# POWER_2_1.net
KiCad netlist of a schematic drawn in Altium Designer
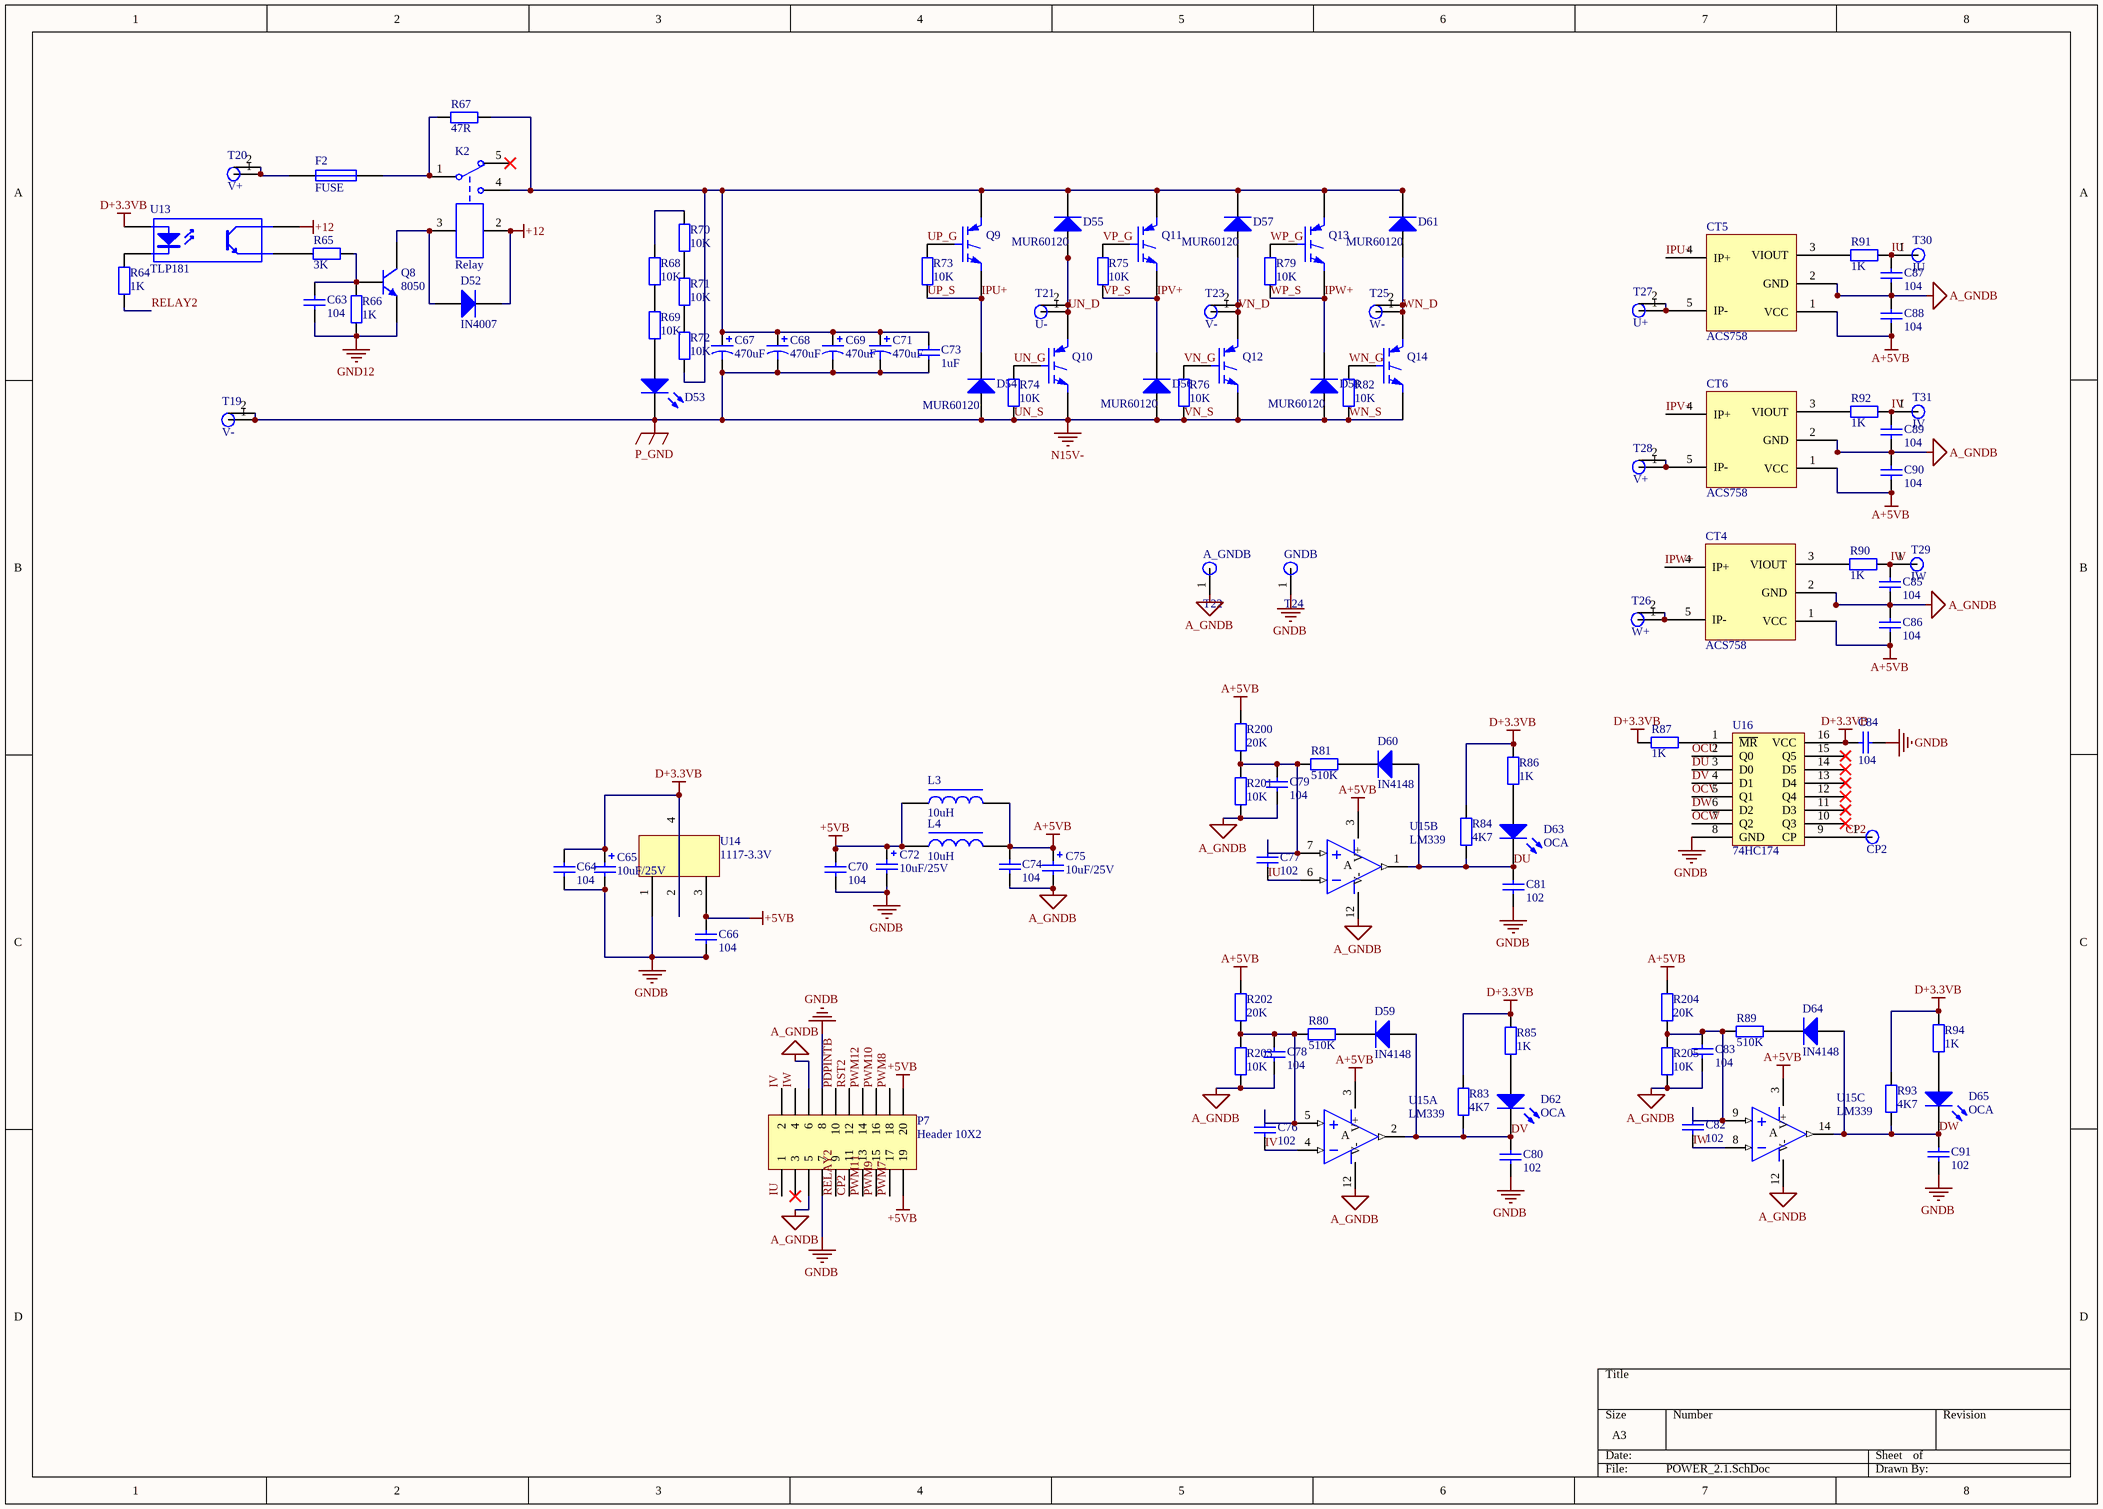
[diagram p0: POWER_2.1.SchDoc]

(export (version "E")
  (design (tool "Eeschema 10.0.6"))
  (components
    (comp (ref "C63")
      (value "104")
      (footprint "C2012-0805")
      (description "普通电容")
      (libsource (lib "Mylib") (part "Cap"))
    )
    (comp (ref "C64")
      (value "104")
      (footprint "C2012-0805")
      (description "普通电容")
      (libsource (lib "*") (part "Cap"))
    )
    (comp (ref "C65")
      (value "10uF/25V")
      (footprint "C_10UF/25V")
      (description "钽电解")
      (libsource (lib "Mylib") (part "Cap tan"))
    )
    (comp (ref "C66")
      (value "104")
      (footprint "C2012-0805")
      (description "普通电容")
      (libsource (lib "*") (part "Cap"))
    )
    (comp (ref "C67")
      (value "470uF")
      (footprint "Rb400mil-450V")
      (description "大电解电容")
      (libsource (lib "Mylib") (part "Cap pol1"))
    )
    (comp (ref "C68")
      (value "470uF")
      (footprint "Rb400mil-450V")
      (description "大电解电容")
      (libsource (lib "Mylib") (part "Cap pol1"))
    )
    (comp (ref "C69")
      (value "470uF")
      (footprint "Rb400mil-450V")
      (description "大电解电容")
      (libsource (lib "Mylib") (part "Cap pol1"))
    )
    (comp (ref "C70")
      (value "104")
      (footprint "C2012-0805")
      (description "普通电容")
      (libsource (lib "*") (part "Cap"))
    )
    (comp (ref "C71")
      (value "470uF")
      (footprint "Rb400mil-450V")
      (description "大电解电容")
      (libsource (lib "Mylib") (part "Cap pol1"))
    )
    (comp (ref "C72")
      (value "10uF/25V")
      (footprint "C_10UF/25V")
      (description "钽电解")
      (libsource (lib "Mylib") (part "Cap tan"))
    )
    (comp (ref "C73")
      (value "1uF")
      (footprint "Rb800mil")
      (description "CBB电容")
      (libsource (lib "Mylib") (part "Cap CBB"))
    )
    (comp (ref "C74")
      (value "104")
      (footprint "C2012-0805")
      (description "普通电容")
      (libsource (lib "*") (part "Cap"))
    )
    (comp (ref "C75")
      (value "10uF/25V")
      (footprint "C_10UF/25V")
      (description "钽电解")
      (libsource (lib "Mylib") (part "Cap tan"))
    )
    (comp (ref "C76")
      (value "102")
      (footprint "C2012-0805")
      (description "普通电容")
      (libsource (lib "*") (part "Cap"))
    )
    (comp (ref "C77")
      (value "102")
      (footprint "C2012-0805")
      (description "普通电容")
      (libsource (lib "*") (part "Cap"))
    )
    (comp (ref "C78")
      (value "104")
      (footprint "C2012-0805")
      (description "普通电容")
      (libsource (lib "*") (part "Cap"))
    )
    (comp (ref "C79")
      (value "104")
      (footprint "C2012-0805")
      (description "普通电容")
      (libsource (lib "*") (part "Cap"))
    )
    (comp (ref "C80")
      (value "102")
      (footprint "C2012-0805")
      (description "普通电容")
      (libsource (lib "*") (part "Cap"))
    )
    (comp (ref "C81")
      (value "102")
      (footprint "C2012-0805")
      (description "普通电容")
      (libsource (lib "*") (part "Cap"))
    )
    (comp (ref "C82")
      (value "102")
      (footprint "C2012-0805")
      (description "普通电容")
      (libsource (lib "*") (part "Cap"))
    )
    (comp (ref "C83")
      (value "104")
      (footprint "C2012-0805")
      (description "普通电容")
      (libsource (lib "*") (part "Cap"))
    )
    (comp (ref "C84")
      (value "104")
      (footprint "C2012-0805")
      (description "普通电容")
      (libsource (lib "*") (part "Cap"))
    )
    (comp (ref "C85")
      (value "104")
      (footprint "C2012-0805")
      (description "普通电容")
      (libsource (lib "Mylib") (part "Cap"))
    )
    (comp (ref "C86")
      (value "104")
      (footprint "C2012-0805")
      (description "普通电容")
      (libsource (lib "Mylib") (part "Cap"))
    )
    (comp (ref "C87")
      (value "104")
      (footprint "C2012-0805")
      (description "普通电容")
      (libsource (lib "Mylib") (part "Cap"))
    )
    (comp (ref "C88")
      (value "104")
      (footprint "C2012-0805")
      (description "普通电容")
      (libsource (lib "Mylib") (part "Cap"))
    )
    (comp (ref "C89")
      (value "104")
      (footprint "C2012-0805")
      (description "普通电容")
      (libsource (lib "Mylib") (part "Cap"))
    )
    (comp (ref "C90")
      (value "104")
      (footprint "C2012-0805")
      (description "普通电容")
      (libsource (lib "Mylib") (part "Cap"))
    )
    (comp (ref "C91")
      (value "102")
      (footprint "C2012-0805")
      (description "普通电容")
      (libsource (lib "*") (part "Cap"))
    )
    (comp (ref "CT4")
      (value "ACS758")
      (footprint "ACS758-LCB-050U-PFF")
      (libsource (lib "Mylib") (part "ACS758"))
    )
    (comp (ref "CT5")
      (value "ACS758")
      (footprint "ACS758-LCB-050U-PFF")
      (libsource (lib "Mylib") (part "ACS758"))
    )
    (comp (ref "CT6")
      (value "ACS758")
      (footprint "ACS758-LCB-050U-PFF")
      (libsource (lib "Mylib") (part "ACS758"))
    )
    (comp (ref "D52")
      (value "IN4007")
      (footprint "DIODE4007")
      (description "普通整流二极管")
      (libsource (lib "Mylib") (part "Diode IN4007"))
    )
    (comp (ref "D53") (value "LED") (footprint "LED-SMD") (libsource (lib "Mylib") (part "LED")))
    (comp (ref "D54")
      (value "MUR60120")
      (footprint "DIO40A1200V")
      (libsource (lib "Mylib") (part "Diode HFA08TB60"))
    )
    (comp (ref "D55")
      (value "MUR60120")
      (footprint "DIO40A1200V")
      (libsource (lib "Mylib") (part "Diode HFA08TB60"))
    )
    (comp (ref "D56")
      (value "MUR60120")
      (footprint "DIO40A1200V")
      (libsource (lib "Mylib") (part "Diode HFA08TB60"))
    )
    (comp (ref "D57")
      (value "MUR60120")
      (footprint "DIO40A1200V")
      (libsource (lib "Mylib") (part "Diode HFA08TB60"))
    )
    (comp (ref "D58")
      (value "MUR60120")
      (footprint "DIO40A1200V")
      (libsource (lib "Mylib") (part "Diode HFA08TB60"))
    )
    (comp (ref "D59")
      (value "IN4148")
      (footprint "IN4148")
      (description "开关二极管")
      (libsource (lib "*") (part "Diode IN4148"))
    )
    (comp (ref "D60")
      (value "IN4148")
      (footprint "IN4148")
      (description "开关二极管")
      (libsource (lib "*") (part "Diode IN4148"))
    )
    (comp (ref "D61")
      (value "MUR60120")
      (footprint "DIO40A1200V")
      (libsource (lib "Mylib") (part "Diode HFA08TB60"))
    )
    (comp (ref "D62") (value "OCA") (footprint "LED-SMD") (libsource (lib "Mylib") (part "LED")))
    (comp (ref "D63") (value "OCA") (footprint "LED-SMD") (libsource (lib "Mylib") (part "LED")))
    (comp (ref "D64")
      (value "IN4148")
      (footprint "IN4148")
      (description "开关二极管")
      (libsource (lib "*") (part "Diode IN4148"))
    )
    (comp (ref "D65") (value "OCA") (footprint "LED-SMD") (libsource (lib "Mylib") (part "LED")))
    (comp (ref "F2") (value "FUSE") (footprint "FUSE") (libsource (lib "Mylib") (part "FUSE")))
    (comp (ref "K2") (value "Relay") (footprint "Relay(30A)") (libsource (lib "Mylib") (part "Relay(30A)")))
    (comp (ref "L3") (value "10uH") (footprint "R2012-0805") (libsource (lib "*") (part "Inductor")))
    (comp (ref "L4") (value "10uH") (footprint "R2012-0805") (libsource (lib "*") (part "Inductor")))
    (comp (ref "P7")
      (value "Header 10X2")
      (footprint "HDR2X10")
      (description "Header, 10-Pin, Dual row")
      (fields (field (name "PUBLISHER") "Altium Limited"))
      (libsource (lib "Miscellaneous Connectors") (part "Header 10X2"))
    )
    (comp (ref "Q8") (value "8050") (footprint "NPN8050") (libsource (lib "Mylib") (part "NPN8050")))
    (comp (ref "Q9") (value "~") (footprint "IGBT TO247 40A 1200V") (libsource (lib "Mylib") (part "IGBT-N")))
    (comp (ref "Q10")
      (value "~")
      (footprint "IGBT TO247 40A 1200V")
      (libsource (lib "Mylib") (part "IGBT-N"))
    )
    (comp (ref "Q11")
      (value "~")
      (footprint "IGBT TO247 40A 1200V")
      (libsource (lib "Mylib") (part "IGBT-N"))
    )
    (comp (ref "Q12")
      (value "~")
      (footprint "IGBT TO247 40A 1200V")
      (libsource (lib "Mylib") (part "IGBT-N"))
    )
    (comp (ref "Q13")
      (value "~")
      (footprint "IGBT TO247 40A 1200V")
      (libsource (lib "Mylib") (part "IGBT-N"))
    )
    (comp (ref "Q14")
      (value "~")
      (footprint "IGBT TO247 40A 1200V")
      (libsource (lib "Mylib") (part "IGBT-N"))
    )
    (comp (ref "R64") (value "1K") (footprint "R2012-0805") (libsource (lib "") (part "Res_3")))
    (comp (ref "R65") (value "3K") (footprint "R2012-0805") (libsource (lib "") (part "Res_2")))
    (comp (ref "R66") (value "1K") (footprint "R2012-0805") (libsource (lib "Mylib") (part "Res")))
    (comp (ref "R67") (value "47R") (footprint "AXIAL-1*1.3") (libsource (lib "") (part "Res_2")))
    (comp (ref "R68") (value "10K") (footprint "R2012-0805") (libsource (lib "Mylib") (part "Res")))
    (comp (ref "R69") (value "10K") (footprint "R2012-0805") (libsource (lib "Mylib") (part "Res")))
    (comp (ref "R70") (value "10K") (footprint "R2012-0805") (libsource (lib "Mylib") (part "Res")))
    (comp (ref "R71") (value "10K") (footprint "R2012-0805") (libsource (lib "Mylib") (part "Res")))
    (comp (ref "R72") (value "10K") (footprint "R2012-0805") (libsource (lib "Mylib") (part "Res")))
    (comp (ref "R73") (value "10K") (footprint "R2012-0805") (libsource (lib "Mylib") (part "Res")))
    (comp (ref "R74") (value "10K") (footprint "R2012-0805") (libsource (lib "Mylib") (part "Res")))
    (comp (ref "R75") (value "10K") (footprint "R2012-0805") (libsource (lib "Mylib") (part "Res")))
    (comp (ref "R76") (value "10K") (footprint "R2012-0805") (libsource (lib "Mylib") (part "Res")))
    (comp (ref "R79") (value "10K") (footprint "R2012-0805") (libsource (lib "Mylib") (part "Res")))
    (comp (ref "R80") (value "510K") (footprint "R2012-0805") (libsource (lib "") (part "Res_1")))
    (comp (ref "R81") (value "510K") (footprint "R2012-0805") (libsource (lib "") (part "Res_1")))
    (comp (ref "R82") (value "10K") (footprint "R2012-0805") (libsource (lib "Mylib") (part "Res")))
    (comp (ref "R83") (value "4K7") (footprint "R2012-0805") (libsource (lib "") (part "Res_2")))
    (comp (ref "R84") (value "4K7") (footprint "R2012-0805") (libsource (lib "") (part "Res_2")))
    (comp (ref "R85") (value "1K") (footprint "R2012-0805") (libsource (lib "") (part "Res_2")))
    (comp (ref "R86") (value "1K") (footprint "R2012-0805") (libsource (lib "") (part "Res_2")))
    (comp (ref "R87") (value "1K") (footprint "R2012-0805") (libsource (lib "") (part "Res_1")))
    (comp (ref "R89") (value "510K") (footprint "R2012-0805") (libsource (lib "") (part "Res_1")))
    (comp (ref "R90") (value "1K") (footprint "R2012-0805") (libsource (lib "") (part "Res_1")))
    (comp (ref "R91") (value "1K") (footprint "R2012-0805") (libsource (lib "") (part "Res_1")))
    (comp (ref "R92") (value "1K") (footprint "R2012-0805") (libsource (lib "") (part "Res_1")))
    (comp (ref "R93") (value "4K7") (footprint "R2012-0805") (libsource (lib "") (part "Res_2")))
    (comp (ref "R94") (value "1K") (footprint "R2012-0805") (libsource (lib "") (part "Res_2")))
    (comp (ref "R200") (value "20K") (footprint "R2012-0805") (libsource (lib "*") (part "Res")))
    (comp (ref "R201") (value "10K") (footprint "R2012-0805") (libsource (lib "*") (part "Res")))
    (comp (ref "R202") (value "20K") (footprint "R2012-0805") (libsource (lib "*") (part "Res")))
    (comp (ref "R203") (value "10K") (footprint "R2012-0805") (libsource (lib "*") (part "Res")))
    (comp (ref "R204") (value "20K") (footprint "R2012-0805") (libsource (lib "*") (part "Res")))
    (comp (ref "R205") (value "10K") (footprint "R2012-0805") (libsource (lib "*") (part "Res")))
    (comp (ref "T19")
      (value "V-")
      (footprint "TEM")
      (description "电源端子")
      (libsource (lib "Mylib") (part "TEM"))
    )
    (comp (ref "T20")
      (value "V+")
      (footprint "TEM")
      (description "电源端子")
      (libsource (lib "Mylib") (part "TEM"))
    )
    (comp (ref "T21")
      (value "U-")
      (footprint "TEM")
      (description "电源端子")
      (libsource (lib "Mylib") (part "TEM"))
    )
    (comp (ref "T22")
      (value "A_GNDB")
      (footprint "PIN1")
      (description "测试脚")
      (libsource (lib "Mylib") (part "TP"))
    )
    (comp (ref "T23")
      (value "V-")
      (footprint "TEM")
      (description "电源端子")
      (libsource (lib "Mylib") (part "TEM"))
    )
    (comp (ref "T24")
      (value "GNDB")
      (footprint "PIN1")
      (description "测试脚")
      (libsource (lib "Mylib") (part "TP"))
    )
    (comp (ref "T25")
      (value "W-")
      (footprint "TEM")
      (description "电源端子")
      (libsource (lib "Mylib") (part "TEM"))
    )
    (comp (ref "T26")
      (value "W+")
      (footprint "TEM")
      (description "电源端子")
      (libsource (lib "Mylib") (part "TEM"))
    )
    (comp (ref "T27")
      (value "U+")
      (footprint "TEM")
      (description "电源端子")
      (libsource (lib "Mylib") (part "TEM"))
    )
    (comp (ref "T28")
      (value "V+")
      (footprint "TEM")
      (description "电源端子")
      (libsource (lib "Mylib") (part "TEM"))
    )
    (comp (ref "T29") (value "IW") (footprint "PIN1") (description "测试脚") (libsource (lib "*") (part "TP")))
    (comp (ref "T30") (value "IU") (footprint "PIN1") (description "测试脚") (libsource (lib "*") (part "TP")))
    (comp (ref "T31") (value "IV") (footprint "PIN1") (description "测试脚") (libsource (lib "*") (part "TP")))
    (comp (ref "TP5")
      (value "CP2")
      (footprint "PIN1")
      (description "测试脚")
      (libsource (lib "Mylib") (part "TP"))
    )
    (comp (ref "U13") (value "TLP181") (footprint "TLP181") (libsource (lib "Mylib") (part "TLP181")))
    (comp (ref "U14") (value "1117-3.3V") (footprint "1117-3.3V") (libsource (lib "Mylib") (part "1117")))
    (comp (ref "U15") (value "LM339") (footprint "LM339") (libsource (lib "Mylib") (part "LM339")))
    (comp (ref "U16")
      (value "74HC174")
      (footprint "74HC174")
      (description "带公共时钟和复位六D触发器")
      (libsource (lib "Mylib") (part "74HC174"))
    )
  )
  (nets
    (net (code "1") (name "+5VB") (class "Default")
      (node (ref "C66") (pin "2") (pinfunction "2_2") (pintype "passive"))
      (node (ref "C70") (pin "2") (pinfunction "2_2") (pintype "passive"))
      (node (ref "C72") (pin "1") (pinfunction "1_1") (pintype "passive"))
      (node (ref "L3") (pin "1") (pinfunction "1_1") (pintype "passive"))
      (node (ref "L4") (pin "1") (pinfunction "1_1") (pintype "passive"))
      (node (ref "P7") (pin "19") (pinfunction "19_19") (pintype "passive"))
      (node (ref "P7") (pin "20") (pinfunction "20_20") (pintype "passive"))
      (node (ref "U14") (pin "3") (pintype "passive"))
    )
    (net (code "2") (name "+12") (class "Default")
      (node (ref "D52") (pin "2") (pinfunction "K_2") (pintype "passive"))
      (node (ref "K2") (pin "2") (pinfunction "2_2") (pintype "passive"))
      (node (ref "U13") (pin "6") (pinfunction "C_6") (pintype "passive"))
    )
    (net (code "3") (name "/CP2") (class "Default")
      (node (ref "P7") (pin "11") (pinfunction "11_11") (pintype "passive"))
      (node (ref "TP5") (pin "1") (pinfunction "A_1") (pintype "passive"))
      (node (ref "U16") (pin "9") (pinfunction "CP_9") (pintype "passive"))
    )
    (net (code "4") (name "/DU") (class "Default")
      (node (ref "C81") (pin "2") (pinfunction "2_2") (pintype "passive"))
      (node (ref "D60") (pin "1") (pinfunction "A_1") (pintype "passive"))
      (node (ref "D63") (pin "2") (pinfunction "K_2") (pintype "passive"))
      (node (ref "R84") (pin "1") (pinfunction "1_1") (pintype "passive"))
      (node (ref "U15") (pin "1") (pinfunction "OUT_1") (pintype "output"))
      (node (ref "U16") (pin "3") (pinfunction "D0_3") (pintype "passive"))
    )
    (net (code "5") (name "/DV") (class "Default")
      (node (ref "C80") (pin "2") (pinfunction "2_2") (pintype "passive"))
      (node (ref "D59") (pin "1") (pinfunction "A_1") (pintype "passive"))
      (node (ref "D62") (pin "2") (pinfunction "K_2") (pintype "passive"))
      (node (ref "R83") (pin "1") (pinfunction "1_1") (pintype "passive"))
      (node (ref "U15") (pin "2") (pinfunction "OUT_2") (pintype "output"))
      (node (ref "U16") (pin "4") (pinfunction "D1_4") (pintype "passive"))
    )
    (net (code "6") (name "/DW") (class "Default")
      (node (ref "C91") (pin "2") (pinfunction "2_2") (pintype "passive"))
      (node (ref "D64") (pin "1") (pinfunction "A_1") (pintype "passive"))
      (node (ref "D65") (pin "2") (pinfunction "K_2") (pintype "passive"))
      (node (ref "R93") (pin "1") (pinfunction "1_1") (pintype "passive"))
      (node (ref "U15") (pin "14") (pinfunction "OUT_14") (pintype "output"))
      (node (ref "U16") (pin "6") (pinfunction "D2_6") (pintype "passive"))
    )
    (net (code "7") (name "/IPU+") (class "Default")
      (node (ref "CT5") (pin "4") (pinfunction "IP+_4") (pintype "passive"))
      (node (ref "D54") (pin "1") (pinfunction "K_1") (pintype "passive"))
      (node (ref "Q9") (pin "3") (pinfunction "E_3") (pintype "passive"))
      (node (ref "R73") (pin "1") (pinfunction "1_1") (pintype "passive"))
    )
    (net (code "8") (name "/IPV+") (class "Default")
      (node (ref "CT6") (pin "4") (pinfunction "IP+_4") (pintype "passive"))
      (node (ref "D56") (pin "1") (pinfunction "K_1") (pintype "passive"))
      (node (ref "Q11") (pin "3") (pinfunction "E_3") (pintype "passive"))
      (node (ref "R75") (pin "1") (pinfunction "1_1") (pintype "passive"))
    )
    (net (code "9") (name "/IPW+") (class "Default")
      (node (ref "CT4") (pin "4") (pinfunction "IP+_4") (pintype "passive"))
      (node (ref "D58") (pin "1") (pinfunction "K_1") (pintype "passive"))
      (node (ref "Q13") (pin "3") (pinfunction "E_3") (pintype "passive"))
      (node (ref "R79") (pin "1") (pinfunction "1_1") (pintype "passive"))
    )
    (net (code "10") (name "/IU") (class "Default")
      (node (ref "C77") (pin "1") (pinfunction "1_1") (pintype "passive"))
      (node (ref "C87") (pin "2") (pinfunction "2_2") (pintype "passive"))
      (node (ref "P7") (pin "1") (pinfunction "1_1") (pintype "passive"))
      (node (ref "R91") (pin "2") (pinfunction "2_2") (pintype "passive"))
      (node (ref "T30") (pin "1") (pinfunction "A_1") (pintype "passive"))
      (node (ref "U15") (pin "6") (pinfunction "IN+_6") (pintype "input"))
    )
    (net (code "11") (name "/IV") (class "Default")
      (node (ref "C76") (pin "1") (pinfunction "1_1") (pintype "passive"))
      (node (ref "C89") (pin "2") (pinfunction "2_2") (pintype "passive"))
      (node (ref "P7") (pin "2") (pinfunction "2_2") (pintype "passive"))
      (node (ref "R92") (pin "2") (pinfunction "2_2") (pintype "passive"))
      (node (ref "T31") (pin "1") (pinfunction "A_1") (pintype "passive"))
      (node (ref "U15") (pin "4") (pinfunction "IN+_4") (pintype "input"))
    )
    (net (code "12") (name "/IW") (class "Default")
      (node (ref "C82") (pin "1") (pinfunction "1_1") (pintype "passive"))
      (node (ref "C85") (pin "2") (pinfunction "2_2") (pintype "passive"))
      (node (ref "P7") (pin "4") (pinfunction "4_4") (pintype "passive"))
      (node (ref "R90") (pin "2") (pinfunction "2_2") (pintype "passive"))
      (node (ref "T29") (pin "1") (pinfunction "A_1") (pintype "passive"))
      (node (ref "U15") (pin "8") (pinfunction "IN+_8") (pintype "input"))
    )
    (net (code "13") (name "/OCU") (class "Default")
      (node (ref "U16") (pin "2") (pinfunction "Q0_2") (pintype "passive"))
    )
    (net (code "14") (name "/OCV") (class "Default")
      (node (ref "U16") (pin "5") (pinfunction "Q1_5") (pintype "passive"))
    )
    (net (code "15") (name "/OCW") (class "Default")
      (node (ref "U16") (pin "7") (pinfunction "Q2_7") (pintype "passive"))
    )
    (net (code "16") (name "/PDPINTB") (class "Default")
      (node (ref "P7") (pin "10") (pinfunction "10_10") (pintype "passive"))
    )
    (net (code "17") (name "/PWM7") (class "Default")
      (node (ref "P7") (pin "17") (pinfunction "17_17") (pintype "passive"))
    )
    (net (code "18") (name "/PWM8") (class "Default")
      (node (ref "P7") (pin "18") (pinfunction "18_18") (pintype "passive"))
    )
    (net (code "19") (name "/PWM9") (class "Default")
      (node (ref "P7") (pin "15") (pinfunction "15_15") (pintype "passive"))
    )
    (net (code "20") (name "/PWM10") (class "Default")
      (node (ref "P7") (pin "16") (pinfunction "16_16") (pintype "passive"))
    )
    (net (code "21") (name "/PWM11") (class "Default")
      (node (ref "P7") (pin "13") (pinfunction "13_13") (pintype "passive"))
    )
    (net (code "22") (name "/PWM12") (class "Default")
      (node (ref "P7") (pin "14") (pinfunction "14_14") (pintype "passive"))
    )
    (net (code "23") (name "/RELAY2") (class "Default")
      (node (ref "P7") (pin "9") (pinfunction "9_9") (pintype "passive"))
      (node (ref "R64") (pin "2") (pinfunction "2_2") (pintype "passive"))
    )
    (net (code "24") (name "/RST2") (class "Default")
      (node (ref "P7") (pin "12") (pinfunction "12_12") (pintype "passive"))
    )
    (net (code "25") (name "/UN_D") (class "Default")
      (node (ref "D55") (pin "3") (pinfunction "A_3") (pintype "passive"))
      (node (ref "Q10") (pin "2") (pinfunction "C_2") (pintype "passive"))
      (node (ref "T21") (pin "1") (pinfunction "A_1") (pintype "passive"))
      (node (ref "T21") (pin "2") (pinfunction "2_2") (pintype "passive"))
    )
    (net (code "26") (name "/UN_G") (class "Default")
      (node (ref "Q10") (pin "1") (pinfunction "G_1") (pintype "passive"))
      (node (ref "R74") (pin "2") (pinfunction "2_2") (pintype "passive"))
    )
    (net (code "27") (name "/UP_G") (class "Default")
      (node (ref "Q9") (pin "1") (pinfunction "G_1") (pintype "passive"))
      (node (ref "R73") (pin "2") (pinfunction "2_2") (pintype "passive"))
    )
    (net (code "28") (name "/VN_D") (class "Default")
      (node (ref "D57") (pin "3") (pinfunction "A_3") (pintype "passive"))
      (node (ref "Q12") (pin "2") (pinfunction "C_2") (pintype "passive"))
      (node (ref "T23") (pin "1") (pinfunction "A_1") (pintype "passive"))
      (node (ref "T23") (pin "2") (pinfunction "2_2") (pintype "passive"))
    )
    (net (code "29") (name "/VN_G") (class "Default")
      (node (ref "Q12") (pin "1") (pinfunction "G_1") (pintype "passive"))
      (node (ref "R76") (pin "2") (pinfunction "2_2") (pintype "passive"))
    )
    (net (code "30") (name "/VP_G") (class "Default")
      (node (ref "Q11") (pin "1") (pinfunction "G_1") (pintype "passive"))
      (node (ref "R75") (pin "2") (pinfunction "2_2") (pintype "passive"))
    )
    (net (code "31") (name "/WN_D") (class "Default")
      (node (ref "D61") (pin "3") (pinfunction "A_3") (pintype "passive"))
      (node (ref "Q14") (pin "2") (pinfunction "C_2") (pintype "passive"))
      (node (ref "T25") (pin "1") (pinfunction "A_1") (pintype "passive"))
      (node (ref "T25") (pin "2") (pinfunction "2_2") (pintype "passive"))
    )
    (net (code "32") (name "/WN_G") (class "Default")
      (node (ref "Q14") (pin "1") (pinfunction "G_1") (pintype "passive"))
      (node (ref "R82") (pin "2") (pinfunction "2_2") (pintype "passive"))
    )
    (net (code "33") (name "/WP_G") (class "Default")
      (node (ref "Q13") (pin "1") (pinfunction "G_1") (pintype "passive"))
      (node (ref "R79") (pin "2") (pinfunction "2_2") (pintype "passive"))
    )
    (net (code "34") (name "A+5VB") (class "Default")
      (node (ref "C74") (pin "2") (pinfunction "2_2") (pintype "passive"))
      (node (ref "C75") (pin "1") (pinfunction "1_1") (pintype "passive"))
      (node (ref "C86") (pin "1") (pinfunction "1_1") (pintype "passive"))
      (node (ref "C88") (pin "1") (pinfunction "1_1") (pintype "passive"))
      (node (ref "C90") (pin "1") (pinfunction "1_1") (pintype "passive"))
      (node (ref "CT4") (pin "1") (pinfunction "VCC_1") (pintype "passive"))
      (node (ref "CT5") (pin "1") (pinfunction "VCC_1") (pintype "passive"))
      (node (ref "CT6") (pin "1") (pinfunction "VCC_1") (pintype "passive"))
      (node (ref "L3") (pin "2") (pinfunction "2_2") (pintype "passive"))
      (node (ref "L4") (pin "2") (pinfunction "2_2") (pintype "passive"))
      (node (ref "R200") (pin "1") (pinfunction "1_1") (pintype "passive"))
      (node (ref "R202") (pin "1") (pinfunction "1_1") (pintype "passive"))
      (node (ref "R204") (pin "1") (pinfunction "1_1") (pintype "passive"))
      (node (ref "U15") (pin "3") (pinfunction "V+_3") (pintype "power_in"))
    )
    (net (code "35") (name "A_GNDB") (class "Default")
      (node (ref "C74") (pin "1") (pinfunction "1_1") (pintype "passive"))
      (node (ref "C75") (pin "2") (pinfunction "2_2") (pintype "passive"))
      (node (ref "C78") (pin "1") (pinfunction "1_1") (pintype "passive"))
      (node (ref "C79") (pin "1") (pinfunction "1_1") (pintype "passive"))
      (node (ref "C83") (pin "1") (pinfunction "1_1") (pintype "passive"))
      (node (ref "C85") (pin "1") (pinfunction "1_1") (pintype "passive"))
      (node (ref "C86") (pin "2") (pinfunction "2_2") (pintype "passive"))
      (node (ref "C87") (pin "1") (pinfunction "1_1") (pintype "passive"))
      (node (ref "C88") (pin "2") (pinfunction "2_2") (pintype "passive"))
      (node (ref "C89") (pin "1") (pinfunction "1_1") (pintype "passive"))
      (node (ref "C90") (pin "2") (pinfunction "2_2") (pintype "passive"))
      (node (ref "CT4") (pin "2") (pinfunction "GND_2") (pintype "passive"))
      (node (ref "CT5") (pin "2") (pinfunction "GND_2") (pintype "passive"))
      (node (ref "CT6") (pin "2") (pinfunction "GND_2") (pintype "passive"))
      (node (ref "P7") (pin "5") (pinfunction "5_5") (pintype "passive"))
      (node (ref "P7") (pin "6") (pinfunction "6_6") (pintype "passive"))
      (node (ref "R201") (pin "2") (pinfunction "2_2") (pintype "passive"))
      (node (ref "R203") (pin "2") (pinfunction "2_2") (pintype "passive"))
      (node (ref "R205") (pin "2") (pinfunction "2_2") (pintype "passive"))
      (node (ref "T22") (pin "1") (pinfunction "A_1") (pintype "passive"))
      (node (ref "U15") (pin "12") (pinfunction "V-_12") (pintype "power_in"))
    )
    (net (code "36") (name "D+3.3VB") (class "Default")
      (node (ref "C64") (pin "2") (pinfunction "2_2") (pintype "passive"))
      (node (ref "C65") (pin "1") (pinfunction "1_1") (pintype "passive"))
      (node (ref "C84") (pin "2") (pinfunction "2_2") (pintype "passive"))
      (node (ref "R83") (pin "2") (pinfunction "2_2") (pintype "passive"))
      (node (ref "R84") (pin "2") (pinfunction "2_2") (pintype "passive"))
      (node (ref "R85") (pin "2") (pinfunction "2_2") (pintype "passive"))
      (node (ref "R86") (pin "2") (pinfunction "2_2") (pintype "passive"))
      (node (ref "R87") (pin "2") (pinfunction "2_2") (pintype "passive"))
      (node (ref "R93") (pin "2") (pinfunction "2_2") (pintype "passive"))
      (node (ref "R94") (pin "2") (pinfunction "2_2") (pintype "passive"))
      (node (ref "U13") (pin "1") (pinfunction "A_1") (pintype "passive"))
      (node (ref "U14") (pin "2") (pintype "passive"))
      (node (ref "U14") (pin "4") (pintype "passive"))
      (node (ref "U16") (pin "16") (pinfunction "VCC_16") (pintype "passive"))
    )
    (net (code "37") (name "GND12") (class "Default")
      (node (ref "C63") (pin "1") (pinfunction "1_1") (pintype "passive"))
      (node (ref "Q8") (pin "2") (pinfunction "E_2") (pintype "passive"))
      (node (ref "R66") (pin "1") (pinfunction "1_1") (pintype "passive"))
    )
    (net (code "38") (name "GNDB") (class "Default")
      (node (ref "C64") (pin "1") (pinfunction "1_1") (pintype "passive"))
      (node (ref "C65") (pin "2") (pinfunction "2_2") (pintype "passive"))
      (node (ref "C66") (pin "1") (pinfunction "1_1") (pintype "passive"))
      (node (ref "C70") (pin "1") (pinfunction "1_1") (pintype "passive"))
      (node (ref "C72") (pin "2") (pinfunction "2_2") (pintype "passive"))
      (node (ref "C80") (pin "1") (pinfunction "1_1") (pintype "passive"))
      (node (ref "C81") (pin "1") (pinfunction "1_1") (pintype "passive"))
      (node (ref "C84") (pin "1") (pinfunction "1_1") (pintype "passive"))
      (node (ref "C91") (pin "1") (pinfunction "1_1") (pintype "passive"))
      (node (ref "P7") (pin "7") (pinfunction "7_7") (pintype "passive"))
      (node (ref "P7") (pin "8") (pinfunction "8_8") (pintype "passive"))
      (node (ref "T24") (pin "1") (pinfunction "A_1") (pintype "passive"))
      (node (ref "U14") (pin "1") (pintype "passive"))
      (node (ref "U16") (pin "8") (pinfunction "GND_8") (pintype "passive"))
    )
    (net (code "39") (name "N15V-") (class "Default")
      (node (ref "C67") (pin "2") (pinfunction "2_2") (pintype "passive"))
      (node (ref "C68") (pin "2") (pinfunction "2_2") (pintype "passive"))
      (node (ref "C69") (pin "2") (pinfunction "2_2") (pintype "passive"))
      (node (ref "C71") (pin "2") (pinfunction "2_2") (pintype "passive"))
      (node (ref "C73") (pin "1") (pinfunction "1_1") (pintype "passive"))
      (node (ref "D53") (pin "2") (pinfunction "K_2") (pintype "passive"))
      (node (ref "D54") (pin "3") (pinfunction "A_3") (pintype "passive"))
      (node (ref "D56") (pin "3") (pinfunction "A_3") (pintype "passive"))
      (node (ref "D58") (pin "3") (pinfunction "A_3") (pintype "passive"))
      (node (ref "Q10") (pin "3") (pinfunction "E_3") (pintype "passive"))
      (node (ref "Q12") (pin "3") (pinfunction "E_3") (pintype "passive"))
      (node (ref "Q14") (pin "3") (pinfunction "E_3") (pintype "passive"))
      (node (ref "R74") (pin "1") (pinfunction "1_1") (pintype "passive"))
      (node (ref "R76") (pin "1") (pinfunction "1_1") (pintype "passive"))
      (node (ref "R82") (pin "1") (pinfunction "1_1") (pintype "passive"))
      (node (ref "T19") (pin "1") (pinfunction "A_1") (pintype "passive"))
      (node (ref "T19") (pin "2") (pinfunction "2_2") (pintype "passive"))
    )
    (net (code "40") (name "Net-(CT4-IP-)") (class "Default")
      (node (ref "CT4") (pin "5") (pinfunction "IP-_5") (pintype "passive"))
      (node (ref "T26") (pin "1") (pinfunction "A_1") (pintype "passive"))
      (node (ref "T26") (pin "2") (pinfunction "2_2") (pintype "passive"))
    )
    (net (code "41") (name "Net-(CT4-VIOUT)") (class "Default")
      (node (ref "CT4") (pin "3") (pinfunction "VIOUT_3") (pintype "passive"))
      (node (ref "R90") (pin "1") (pinfunction "1_1") (pintype "passive"))
    )
    (net (code "42") (name "Net-(CT5-IP-)") (class "Default")
      (node (ref "CT5") (pin "5") (pinfunction "IP-_5") (pintype "passive"))
      (node (ref "T27") (pin "1") (pinfunction "A_1") (pintype "passive"))
      (node (ref "T27") (pin "2") (pinfunction "2_2") (pintype "passive"))
    )
    (net (code "43") (name "Net-(CT5-VIOUT)") (class "Default")
      (node (ref "CT5") (pin "3") (pinfunction "VIOUT_3") (pintype "passive"))
      (node (ref "R91") (pin "1") (pinfunction "1_1") (pintype "passive"))
    )
    (net (code "44") (name "Net-(CT6-IP-)") (class "Default")
      (node (ref "CT6") (pin "5") (pinfunction "IP-_5") (pintype "passive"))
      (node (ref "T28") (pin "1") (pinfunction "A_1") (pintype "passive"))
      (node (ref "T28") (pin "2") (pinfunction "2_2") (pintype "passive"))
    )
    (net (code "45") (name "Net-(CT6-VIOUT)") (class "Default")
      (node (ref "CT6") (pin "3") (pinfunction "VIOUT_3") (pintype "passive"))
      (node (ref "R92") (pin "1") (pinfunction "1_1") (pintype "passive"))
    )
    (net (code "46") (name "Net-(D52-A)") (class "Default")
      (node (ref "D52") (pin "1") (pinfunction "A_1") (pintype "passive"))
      (node (ref "K2") (pin "3") (pinfunction "3_3") (pintype "passive"))
      (node (ref "Q8") (pin "3") (pinfunction "C_3") (pintype "passive"))
    )
    (net (code "47") (name "Net-(D53-A)") (class "Default")
      (node (ref "D53") (pin "1") (pinfunction "A_1") (pintype "passive"))
      (node (ref "R69") (pin "1") (pinfunction "1_1") (pintype "passive"))
    )
    (net (code "48") (name "Net-(D55-K)") (class "Default")
      (node (ref "C67") (pin "1") (pinfunction "1_1") (pintype "passive"))
      (node (ref "C68") (pin "1") (pinfunction "1_1") (pintype "passive"))
      (node (ref "C69") (pin "1") (pinfunction "1_1") (pintype "passive"))
      (node (ref "C71") (pin "1") (pinfunction "1_1") (pintype "passive"))
      (node (ref "C73") (pin "2") (pinfunction "2_2") (pintype "passive"))
      (node (ref "D55") (pin "1") (pinfunction "K_1") (pintype "passive"))
      (node (ref "D57") (pin "1") (pinfunction "K_1") (pintype "passive"))
      (node (ref "D61") (pin "1") (pinfunction "K_1") (pintype "passive"))
      (node (ref "K2") (pin "4") (pinfunction "4_4") (pintype "passive"))
      (node (ref "Q11") (pin "2") (pinfunction "C_2") (pintype "passive"))
      (node (ref "Q13") (pin "2") (pinfunction "C_2") (pintype "passive"))
      (node (ref "Q9") (pin "2") (pinfunction "C_2") (pintype "passive"))
      (node (ref "R67") (pin "1") (pinfunction "1_1") (pintype "passive"))
      (node (ref "R72") (pin "1") (pinfunction "1_1") (pintype "passive"))
    )
    (net (code "49") (name "Net-(D59-K)") (class "Default")
      (node (ref "D59") (pin "2") (pinfunction "K_2") (pintype "passive"))
      (node (ref "R80") (pin "1") (pinfunction "1_1") (pintype "passive"))
    )
    (net (code "50") (name "Net-(D60-K)") (class "Default")
      (node (ref "D60") (pin "2") (pinfunction "K_2") (pintype "passive"))
      (node (ref "R81") (pin "1") (pinfunction "1_1") (pintype "passive"))
    )
    (net (code "51") (name "Net-(D62-A)") (class "Default")
      (node (ref "D62") (pin "1") (pinfunction "A_1") (pintype "passive"))
      (node (ref "R85") (pin "1") (pinfunction "1_1") (pintype "passive"))
    )
    (net (code "52") (name "Net-(D63-A)") (class "Default")
      (node (ref "D63") (pin "1") (pinfunction "A_1") (pintype "passive"))
      (node (ref "R86") (pin "1") (pinfunction "1_1") (pintype "passive"))
    )
    (net (code "53") (name "Net-(D64-K)") (class "Default")
      (node (ref "D64") (pin "2") (pinfunction "K_2") (pintype "passive"))
      (node (ref "R89") (pin "1") (pinfunction "1_1") (pintype "passive"))
    )
    (net (code "54") (name "Net-(D65-A)") (class "Default")
      (node (ref "D65") (pin "1") (pinfunction "A_1") (pintype "passive"))
      (node (ref "R94") (pin "1") (pinfunction "1_1") (pintype "passive"))
    )
    (net (code "55") (name "Net-(F2-Pad2)") (class "Default")
      (node (ref "F2") (pin "2") (pinfunction "2_2") (pintype "passive"))
      (node (ref "K2") (pin "1") (pinfunction "1_1") (pintype "passive"))
      (node (ref "R67") (pin "2") (pinfunction "2_2") (pintype "passive"))
    )
    (net (code "56") (name "Net-(Q8-B)") (class "Default")
      (node (ref "C63") (pin "2") (pinfunction "2_2") (pintype "passive"))
      (node (ref "Q8") (pin "1") (pinfunction "B_1") (pintype "passive"))
      (node (ref "R65") (pin "1") (pinfunction "1_1") (pintype "passive"))
      (node (ref "R66") (pin "2") (pinfunction "2_2") (pintype "passive"))
    )
    (net (code "57") (name "Net-(R68-Pad1)") (class "Default")
      (node (ref "R68") (pin "1") (pinfunction "1_1") (pintype "passive"))
      (node (ref "R69") (pin "2") (pinfunction "2_2") (pintype "passive"))
    )
    (net (code "58") (name "Net-(R68-Pad2)") (class "Default")
      (node (ref "R68") (pin "2") (pinfunction "2_2") (pintype "passive"))
      (node (ref "R70") (pin "2") (pinfunction "2_2") (pintype "passive"))
    )
    (net (code "59") (name "Net-(R70-Pad1)") (class "Default")
      (node (ref "R70") (pin "1") (pinfunction "1_1") (pintype "passive"))
      (node (ref "R71") (pin "2") (pinfunction "2_2") (pintype "passive"))
    )
    (net (code "60") (name "Net-(R71-Pad1)") (class "Default")
      (node (ref "R71") (pin "1") (pinfunction "1_1") (pintype "passive"))
      (node (ref "R72") (pin "2") (pinfunction "2_2") (pintype "passive"))
    )
    (net (code "61") (name "Net-(T20-A)") (class "Default")
      (node (ref "F2") (pin "1") (pinfunction "1_1") (pintype "passive"))
      (node (ref "T20") (pin "1") (pinfunction "A_1") (pintype "passive"))
      (node (ref "T20") (pin "2") (pinfunction "2_2") (pintype "passive"))
    )
    (net (code "62") (name "Net-(U13-E)") (class "Default")
      (node (ref "R65") (pin "2") (pinfunction "2_2") (pintype "passive"))
      (node (ref "U13") (pin "4") (pinfunction "E_4") (pintype "passive"))
    )
    (net (code "63") (name "Net-(U13-K)") (class "Default")
      (node (ref "R64") (pin "1") (pinfunction "1_1") (pintype "passive"))
      (node (ref "U13") (pin "3") (pinfunction "K_3") (pintype "passive"))
    )
    (net (code "64") (name "Net-(U15A-IN-)") (class "Default")
      (node (ref "C76") (pin "2") (pinfunction "2_2") (pintype "passive"))
      (node (ref "C78") (pin "2") (pinfunction "2_2") (pintype "passive"))
      (node (ref "R202") (pin "2") (pinfunction "2_2") (pintype "passive"))
      (node (ref "R203") (pin "1") (pinfunction "1_1") (pintype "passive"))
      (node (ref "R80") (pin "2") (pinfunction "2_2") (pintype "passive"))
      (node (ref "U15") (pin "5") (pinfunction "IN-_5") (pintype "input"))
    )
    (net (code "65") (name "Net-(U15B-IN-)") (class "Default")
      (node (ref "C77") (pin "2") (pinfunction "2_2") (pintype "passive"))
      (node (ref "C79") (pin "2") (pinfunction "2_2") (pintype "passive"))
      (node (ref "R200") (pin "2") (pinfunction "2_2") (pintype "passive"))
      (node (ref "R201") (pin "1") (pinfunction "1_1") (pintype "passive"))
      (node (ref "R81") (pin "2") (pinfunction "2_2") (pintype "passive"))
      (node (ref "U15") (pin "7") (pinfunction "IN-_7") (pintype "input"))
    )
    (net (code "66") (name "Net-(U15C-IN-)") (class "Default")
      (node (ref "C82") (pin "2") (pinfunction "2_2") (pintype "passive"))
      (node (ref "C83") (pin "2") (pinfunction "2_2") (pintype "passive"))
      (node (ref "R204") (pin "2") (pinfunction "2_2") (pintype "passive"))
      (node (ref "R205") (pin "1") (pinfunction "1_1") (pintype "passive"))
      (node (ref "R89") (pin "2") (pinfunction "2_2") (pintype "passive"))
      (node (ref "U15") (pin "9") (pinfunction "IN-_9") (pintype "input"))
    )
    (net (code "67") (name "Net-(U16-~{MR})") (class "Default")
      (node (ref "R87") (pin "1") (pinfunction "1_1") (pintype "passive"))
      (node (ref "U16") (pin "1") (pinfunction "~{MR}_1") (pintype "passive"))
    )
    (net (code "68") (name "unconnected-(K2-Pad5)") (class "Default")
      (node (ref "K2") (pin "5") (pinfunction "5_5") (pintype "passive+no_connect"))
    )
    (net (code "69") (name "unconnected-(P7-Pad3)") (class "Default")
      (node (ref "P7") (pin "3") (pinfunction "3_3") (pintype "passive+no_connect"))
    )
    (net (code "70") (name "unconnected-(U16-D3-Pad11)") (class "Default")
      (node (ref "U16") (pin "11") (pinfunction "D3_11") (pintype "passive+no_connect"))
    )
    (net (code "71") (name "unconnected-(U16-D4-Pad13)") (class "Default")
      (node (ref "U16") (pin "13") (pinfunction "D4_13") (pintype "passive+no_connect"))
    )
    (net (code "72") (name "unconnected-(U16-D5-Pad14)") (class "Default")
      (node (ref "U16") (pin "14") (pinfunction "D5_14") (pintype "passive+no_connect"))
    )
    (net (code "73") (name "unconnected-(U16-Q3-Pad10)") (class "Default")
      (node (ref "U16") (pin "10") (pinfunction "Q3_10") (pintype "passive+no_connect"))
    )
    (net (code "74") (name "unconnected-(U16-Q4-Pad12)") (class "Default")
      (node (ref "U16") (pin "12") (pinfunction "Q4_12") (pintype "passive+no_connect"))
    )
    (net (code "75") (name "unconnected-(U16-Q5-Pad15)") (class "Default")
      (node (ref "U16") (pin "15") (pinfunction "Q5_15") (pintype "passive+no_connect"))
    )
  )
)
